# femtoUSB_r1_0_1-rgb.net
KiCad netlist of a schematic drawn in EAGLE
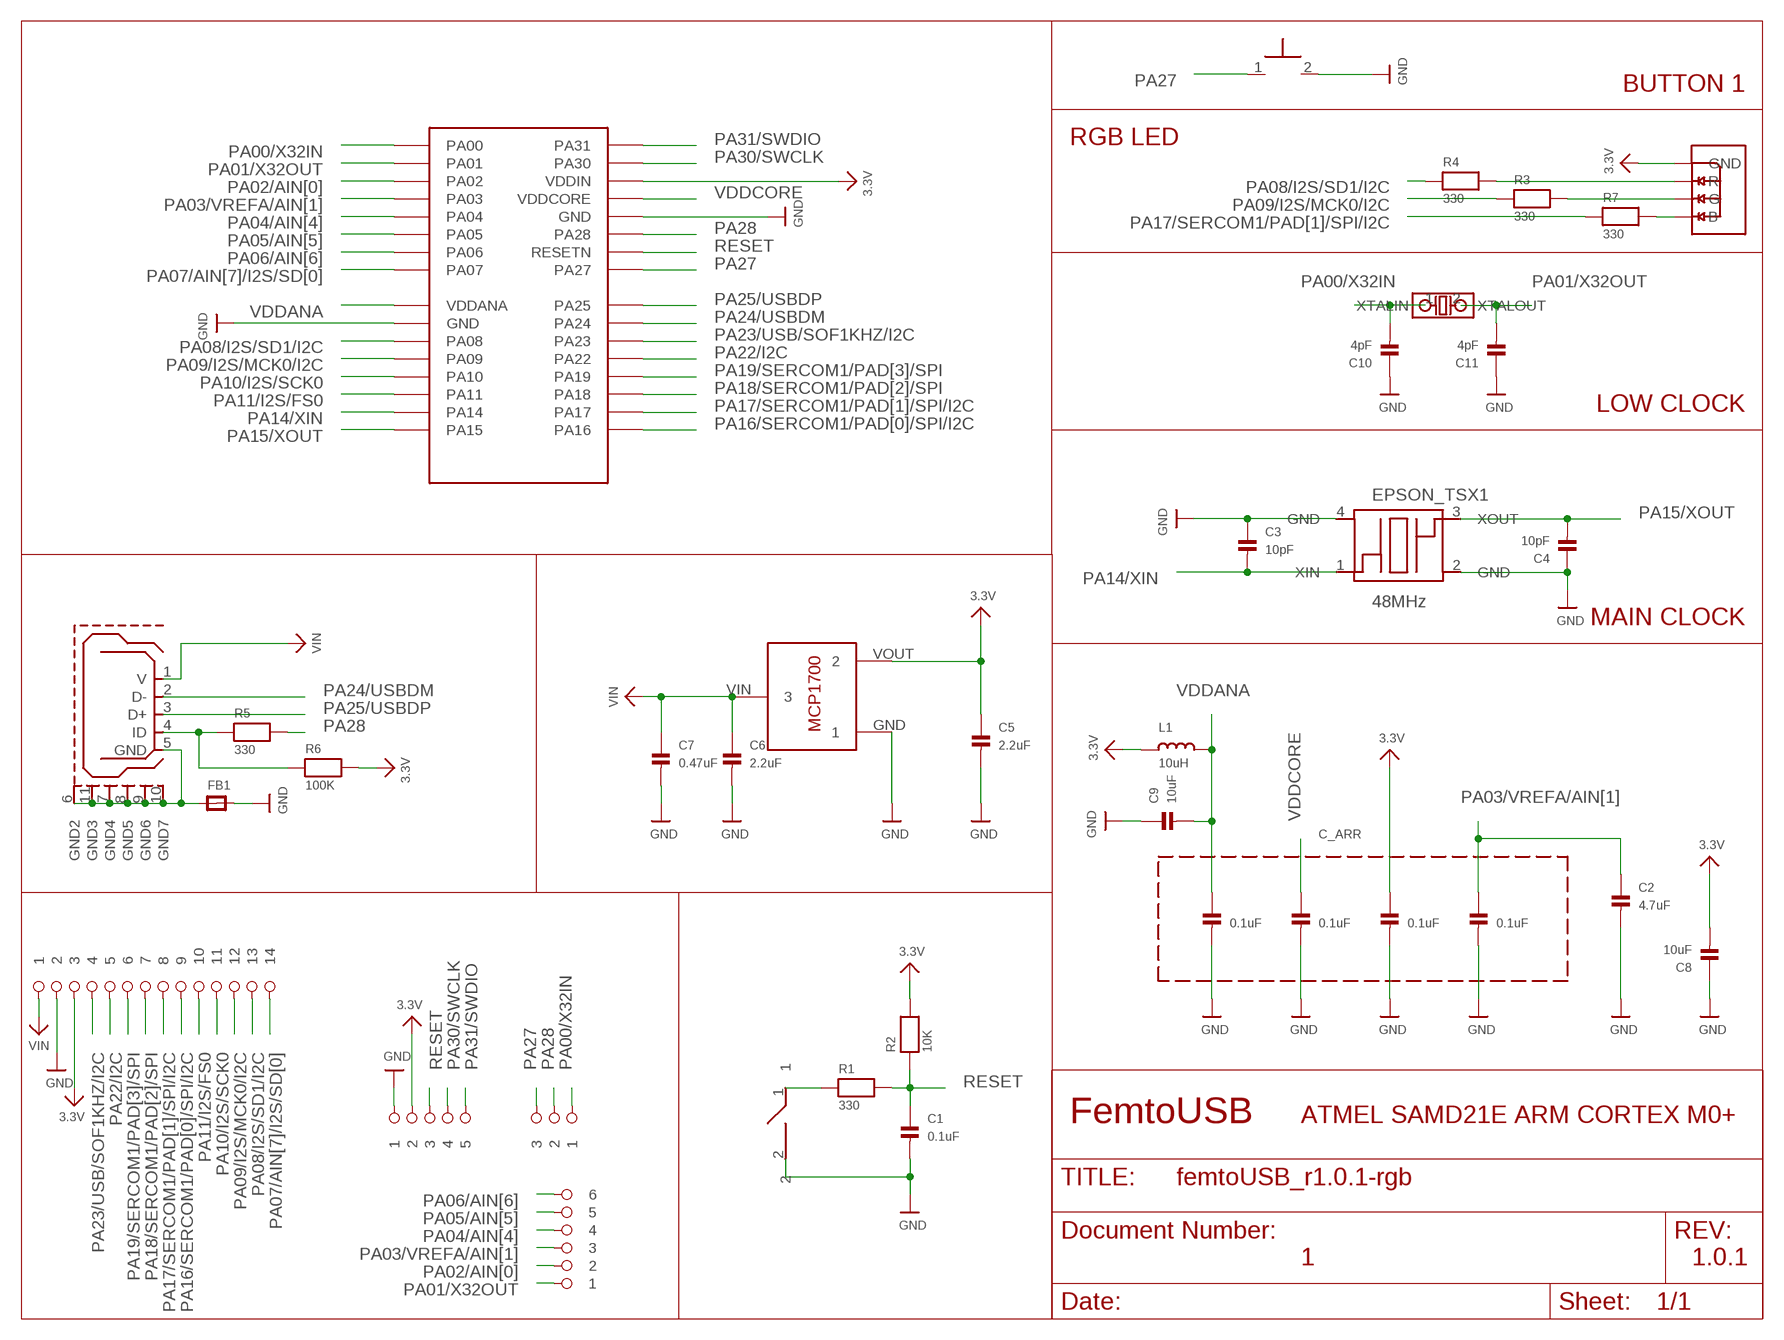
[diagram p0: schematic, sheet 1]

(export (version "E")
  (design (tool "Eeschema 10.0.6"))
  (components
    (comp (ref "BTN_BOOT")
      (value "TACTILE_SWITCH_NO_GND_NO_BOSS")
      (footprint "eagle-import:SIDE_ACT_NO_GND_NO_BOSS")
      (libsource (lib "eagle-import") (part "TACTILE_SWITCH_NO_GND_NO_BOSS"))
    )
    (comp (ref "C1")
      (value "0.1uF")
      (footprint "eagle-import:_0402MP")
      (libsource (lib "eagle-import") (part "CAP_CERAMIC_0402MP"))
    )
    (comp (ref "C2")
      (value "4.7uF")
      (footprint "eagle-import:_0402MP")
      (libsource (lib "eagle-import") (part "CAP_CERAMIC_0402MP"))
    )
    (comp (ref "C3")
      (value "10pF")
      (footprint "eagle-import:_0402MP")
      (libsource (lib "eagle-import") (part "CAP_CERAMIC_0402MP"))
    )
    (comp (ref "C4")
      (value "10pF")
      (footprint "eagle-import:_0402MP")
      (libsource (lib "eagle-import") (part "CAP_CERAMIC_0402MP"))
    )
    (comp (ref "C5")
      (value "2.2uF")
      (footprint "eagle-import:_0402MP")
      (libsource (lib "eagle-import") (part "CAP_CERAMIC_0402MP"))
    )
    (comp (ref "C6")
      (value "2.2uF")
      (footprint "eagle-import:_0402MP")
      (libsource (lib "eagle-import") (part "CAP_CERAMIC_0402MP"))
    )
    (comp (ref "C7")
      (value "0.47uF")
      (footprint "eagle-import:_0402MP")
      (libsource (lib "eagle-import") (part "CAP_CERAMIC_0402MP"))
    )
    (comp (ref "C8")
      (value "10uF")
      (footprint "eagle-import:_0402MP")
      (libsource (lib "eagle-import") (part "CAP_CERAMIC_0402MP"))
    )
    (comp (ref "C9")
      (value "10uF")
      (footprint "eagle-import:_0402MP")
      (libsource (lib "eagle-import") (part "CAP_CERAMIC_0402MP"))
    )
    (comp (ref "C10")
      (value "4pF")
      (footprint "eagle-import:_0402MP")
      (libsource (lib "eagle-import") (part "CAP_CERAMIC_0402MP"))
    )
    (comp (ref "C11")
      (value "4pF")
      (footprint "eagle-import:_0402MP")
      (libsource (lib "eagle-import") (part "CAP_CERAMIC_0402MP"))
    )
    (comp (ref "C_ARR")
      (value "0.1uF")
      (footprint "eagle-import:CAPACITOR_ARRAY_1206_MONO_1X4")
      (libsource (lib "eagle-import") (part "KEMET_CERAMIC_CAPACITOR_ARRAY_1X4"))
    )
    (comp (ref "EPSON_TSX1")
      (value "48MHz")
      (footprint "eagle-import:TSX-3225")
      (libsource (lib "eagle-import") (part "TSX-3225"))
    )
    (comp (ref "FB1")
      (value "FERRITE_0603MP")
      (footprint "eagle-import:_0603MP")
      (libsource (lib "eagle-import") (part "FERRITE_0603MP"))
    )
    (comp (ref "IC1")
      (value "ATSAMD21E18A-MUT")
      (footprint "eagle-import:QFN32")
      (libsource (lib "eagle-import") (part "ATSAMD21E18A-MUT"))
    )
    (comp (ref "L1")
      (value "10uH")
      (footprint "eagle-import:_0603MP")
      (libsource (lib "eagle-import") (part "INDUCTOR_0603MP"))
    )
    (comp (ref "LDO_VREG")
      (value "MCP1700T-3302E/TT")
      (footprint "eagle-import:MCP1700T-3302E_TT")
      (libsource (lib "eagle-import") (part "MCP1700T-3302E/TT"))
    )
    (comp (ref "MICRO_B_USB")
      (value "USB_MICROB")
      (footprint "eagle-import:USB_MICROB_PACKAGE")
      (libsource (lib "eagle-import") (part "USB_MICROB"))
    )
    (comp (ref "OSC32K")
      (value "ABS06-107-32.768KHZ-T")
      (footprint "eagle-import:ABS06-107-32.768KHZ-T")
      (libsource (lib "eagle-import") (part "ABS06-107-32.768KHZ-T"))
    )
    (comp (ref "PIN_1X3")
      (value "1X3_ROUND")
      (footprint "eagle-import:1X3_ROUND")
      (libsource (lib "eagle-import") (part "1X3_ROUND"))
    )
    (comp (ref "PIN_1X5")
      (value "1X5_ROUND")
      (footprint "eagle-import:1X5_ROUND")
      (libsource (lib "eagle-import") (part "1X5_ROUND"))
    )
    (comp (ref "PIN_1X6")
      (value "1X6_ROUND")
      (footprint "eagle-import:1X6_ROUND")
      (libsource (lib "eagle-import") (part "1X6_ROUND"))
    )
    (comp (ref "PIN_1X14")
      (value "1X14_ROUND")
      (footprint "eagle-import:1X14_ROUND")
      (libsource (lib "eagle-import") (part "1X14_ROUND"))
    )
    (comp (ref "R1")
      (value "330")
      (footprint "eagle-import:_0402MP")
      (libsource (lib "eagle-import") (part "RESISTOR_0402MP"))
    )
    (comp (ref "R2")
      (value "10K")
      (footprint "eagle-import:_0402MP")
      (libsource (lib "eagle-import") (part "RESISTOR_0402MP"))
    )
    (comp (ref "R3")
      (value "330")
      (footprint "eagle-import:_0402MP")
      (libsource (lib "eagle-import") (part "RESISTOR_0402MP"))
    )
    (comp (ref "R4")
      (value "330")
      (footprint "eagle-import:_0402MP")
      (libsource (lib "eagle-import") (part "RESISTOR_0402MP"))
    )
    (comp (ref "R5")
      (value "330")
      (footprint "eagle-import:_0402MP")
      (libsource (lib "eagle-import") (part "RESISTOR_0402MP"))
    )
    (comp (ref "R6")
      (value "100K")
      (footprint "eagle-import:_0402MP")
      (libsource (lib "eagle-import") (part "RESISTOR_0402MP"))
    )
    (comp (ref "R7")
      (value "330")
      (footprint "eagle-import:_0402MP")
      (libsource (lib "eagle-import") (part "RESISTOR_0402MP"))
    )
    (comp (ref "RGBLED")
      (value "LRTB_R48G")
      (footprint "eagle-import:LRTB_R48G")
      (libsource (lib "eagle-import") (part "LRTB_R48G"))
    )
    (comp (ref "SJ_RESET")
      (value "SPST_SMD")
      (footprint "eagle-import:SPST_SMD")
      (libsource (lib "eagle-import") (part "SPST_SMD"))
    )
  )
  (nets
    (net (code "1") (name "/PA00{slash}X32IN") (class "Default")
      (node (ref "C10") (pin "2") (pinfunction "P$2_2") (pintype "passive"))
      (node (ref "IC1") (pin "1") (pinfunction "PA00_1") (pintype "bidirectional"))
      (node (ref "OSC32K") (pin "1") (pinfunction "XTALIN_1") (pintype "bidirectional"))
      (node (ref "PIN_1X3") (pin "P$1") (pinfunction "1_P$1") (pintype "bidirectional"))
    )
    (net (code "2") (name "/PA01{slash}X32OUT") (class "Default")
      (node (ref "C11") (pin "2") (pinfunction "P$2_2") (pintype "passive"))
      (node (ref "IC1") (pin "2") (pinfunction "PA01_2") (pintype "bidirectional"))
      (node (ref "OSC32K") (pin "2") (pinfunction "XTALOUT_2") (pintype "bidirectional"))
      (node (ref "PIN_1X6") (pin "P$1") (pinfunction "1_P$1") (pintype "bidirectional"))
    )
    (net (code "3") (name "/PA02{slash}AIN[0]") (class "Default")
      (node (ref "IC1") (pin "3") (pinfunction "PA02_3") (pintype "bidirectional"))
      (node (ref "PIN_1X6") (pin "P$2") (pinfunction "2_P$2") (pintype "bidirectional"))
    )
    (net (code "4") (name "/PA03{slash}VREFA{slash}AIN[1]") (class "Default")
      (node (ref "C2") (pin "1") (pinfunction "P$1_1") (pintype "passive"))
      (node (ref "C_ARR") (pin "7") (pinfunction "P$7_7") (pintype "passive"))
      (node (ref "IC1") (pin "4") (pinfunction "PA03_4") (pintype "bidirectional"))
      (node (ref "PIN_1X6") (pin "P$3") (pinfunction "3_P$3") (pintype "bidirectional"))
    )
    (net (code "5") (name "/PA04{slash}AIN[4]") (class "Default")
      (node (ref "IC1") (pin "5") (pinfunction "PA04_5") (pintype "bidirectional"))
      (node (ref "PIN_1X6") (pin "P$4") (pinfunction "4_P$4") (pintype "bidirectional"))
    )
    (net (code "6") (name "/PA05{slash}AIN[5]") (class "Default")
      (node (ref "IC1") (pin "6") (pinfunction "PA05_6") (pintype "bidirectional"))
      (node (ref "PIN_1X6") (pin "P$5") (pinfunction "5_P$5") (pintype "bidirectional"))
    )
    (net (code "7") (name "/PA06{slash}AIN[6]") (class "Default")
      (node (ref "IC1") (pin "7") (pinfunction "PA06_7") (pintype "bidirectional"))
      (node (ref "PIN_1X6") (pin "P$6") (pinfunction "6_P$6") (pintype "bidirectional"))
    )
    (net (code "8") (name "/PA07{slash}AIN[7]{slash}I2S{slash}SD[0]") (class "Default")
      (node (ref "IC1") (pin "8") (pinfunction "PA07_8") (pintype "bidirectional"))
      (node (ref "PIN_1X14") (pin "P$14") (pinfunction "14_P$14") (pintype "bidirectional"))
    )
    (net (code "9") (name "/PA08{slash}I2S{slash}SD1{slash}I2C") (class "Default")
      (node (ref "IC1") (pin "11") (pinfunction "PA08_11") (pintype "bidirectional"))
      (node (ref "PIN_1X14") (pin "P$13") (pinfunction "13_P$13") (pintype "bidirectional"))
      (node (ref "R4") (pin "1") (pinfunction "1_1") (pintype "passive"))
    )
    (net (code "10") (name "/PA09{slash}I2S{slash}MCK0{slash}I2C") (class "Default")
      (node (ref "IC1") (pin "12") (pinfunction "PA09_12") (pintype "bidirectional"))
      (node (ref "PIN_1X14") (pin "P$12") (pinfunction "12_P$12") (pintype "bidirectional"))
      (node (ref "R3") (pin "1") (pinfunction "1_1") (pintype "passive"))
    )
    (net (code "11") (name "/PA10{slash}I2S{slash}SCK0") (class "Default")
      (node (ref "IC1") (pin "13") (pinfunction "PA10_13") (pintype "bidirectional"))
      (node (ref "PIN_1X14") (pin "P$11") (pinfunction "11_P$11") (pintype "bidirectional"))
    )
    (net (code "12") (name "/PA11{slash}I2S{slash}FS0") (class "Default")
      (node (ref "IC1") (pin "14") (pinfunction "PA11_14") (pintype "bidirectional"))
      (node (ref "PIN_1X14") (pin "P$10") (pinfunction "10_P$10") (pintype "bidirectional"))
    )
    (net (code "13") (name "/PA14{slash}XIN") (class "Default")
      (node (ref "C3") (pin "2") (pinfunction "P$2_2") (pintype "passive"))
      (node (ref "EPSON_TSX1") (pin "1") (pinfunction "XIN_1") (pintype "bidirectional"))
      (node (ref "IC1") (pin "15") (pinfunction "PA14_15") (pintype "bidirectional"))
    )
    (net (code "14") (name "/PA15{slash}XOUT") (class "Default")
      (node (ref "C4") (pin "2") (pinfunction "P$2_2") (pintype "passive"))
      (node (ref "EPSON_TSX1") (pin "3") (pinfunction "XOUT_3") (pintype "bidirectional"))
      (node (ref "IC1") (pin "16") (pinfunction "PA15_16") (pintype "bidirectional"))
    )
    (net (code "15") (name "/PA16{slash}SERCOM1{slash}PAD[0]{slash}SPI{slash}I2C") (class "Default")
      (node (ref "IC1") (pin "17") (pinfunction "PA16_17") (pintype "bidirectional"))
      (node (ref "PIN_1X14") (pin "P$9") (pinfunction "9_P$9") (pintype "bidirectional"))
    )
    (net (code "16") (name "/PA17{slash}SERCOM1{slash}PAD[1]{slash}SPI{slash}I2C") (class "Default")
      (node (ref "IC1") (pin "18") (pinfunction "PA17_18") (pintype "bidirectional"))
      (node (ref "PIN_1X14") (pin "P$8") (pinfunction "8_P$8") (pintype "bidirectional"))
      (node (ref "R7") (pin "1") (pinfunction "1_1") (pintype "passive"))
    )
    (net (code "17") (name "/PA18{slash}SERCOM1{slash}PAD[2]{slash}SPI") (class "Default")
      (node (ref "IC1") (pin "19") (pinfunction "PA18_19") (pintype "bidirectional"))
      (node (ref "PIN_1X14") (pin "P$7") (pinfunction "7_P$7") (pintype "bidirectional"))
    )
    (net (code "18") (name "/PA19{slash}SERCOM1{slash}PAD[3]{slash}SPI") (class "Default")
      (node (ref "IC1") (pin "20") (pinfunction "PA19_20") (pintype "bidirectional"))
      (node (ref "PIN_1X14") (pin "P$6") (pinfunction "6_P$6") (pintype "bidirectional"))
    )
    (net (code "19") (name "/PA22{slash}I2C") (class "Default")
      (node (ref "IC1") (pin "21") (pinfunction "PA22_21") (pintype "bidirectional"))
      (node (ref "PIN_1X14") (pin "P$5") (pinfunction "5_P$5") (pintype "bidirectional"))
    )
    (net (code "20") (name "/PA23{slash}USB{slash}SOF1KHZ{slash}I2C") (class "Default")
      (node (ref "IC1") (pin "22") (pinfunction "PA23_22") (pintype "bidirectional"))
      (node (ref "PIN_1X14") (pin "P$4") (pinfunction "4_P$4") (pintype "bidirectional"))
    )
    (net (code "21") (name "/PA24{slash}USBDM") (class "Default")
      (node (ref "IC1") (pin "23") (pinfunction "PA24_23") (pintype "bidirectional"))
      (node (ref "MICRO_B_USB") (pin "2") (pinfunction "D-_2") (pintype "bidirectional"))
    )
    (net (code "22") (name "/PA25{slash}USBDP") (class "Default")
      (node (ref "IC1") (pin "24") (pinfunction "PA25_24") (pintype "bidirectional"))
      (node (ref "MICRO_B_USB") (pin "3") (pinfunction "D+_3") (pintype "bidirectional"))
    )
    (net (code "23") (name "/PA27") (class "Default")
      (node (ref "BTN_BOOT") (pin "1") (pinfunction "1_1") (pintype "bidirectional"))
      (node (ref "IC1") (pin "25") (pinfunction "PA27_25") (pintype "bidirectional"))
      (node (ref "PIN_1X3") (pin "P$3") (pinfunction "3_P$3") (pintype "bidirectional"))
    )
    (net (code "24") (name "/PA28") (class "Default")
      (node (ref "IC1") (pin "27") (pinfunction "PA28_27") (pintype "bidirectional"))
      (node (ref "PIN_1X3") (pin "P$2") (pinfunction "2_P$2") (pintype "bidirectional"))
      (node (ref "R5") (pin "2") (pinfunction "2_2") (pintype "passive"))
    )
    (net (code "25") (name "/PA30{slash}SWCLK") (class "Default")
      (node (ref "IC1") (pin "31") (pinfunction "PA30_31") (pintype "bidirectional"))
      (node (ref "PIN_1X5") (pin "P$4") (pinfunction "4_P$4") (pintype "bidirectional"))
    )
    (net (code "26") (name "/PA31{slash}SWDIO") (class "Default")
      (node (ref "IC1") (pin "32") (pinfunction "PA31_32") (pintype "bidirectional"))
      (node (ref "PIN_1X5") (pin "P$5") (pinfunction "5_P$5") (pintype "bidirectional"))
    )
    (net (code "27") (name "/RESET") (class "Default")
      (node (ref "C1") (pin "1") (pinfunction "P$1_1") (pintype "passive"))
      (node (ref "IC1") (pin "26") (pinfunction "RESETN_26") (pintype "bidirectional"))
      (node (ref "PIN_1X5") (pin "P$3") (pinfunction "3_P$3") (pintype "bidirectional"))
      (node (ref "R1") (pin "2") (pinfunction "2_2") (pintype "passive"))
      (node (ref "R2") (pin "1") (pinfunction "1_1") (pintype "passive"))
    )
    (net (code "28") (name "/VDDANA") (class "Default")
      (node (ref "C9") (pin "2") (pinfunction "P$2_2") (pintype "passive"))
      (node (ref "C_ARR") (pin "1") (pinfunction "P$1_1") (pintype "passive"))
      (node (ref "IC1") (pin "9") (pinfunction "VDDANA_9") (pintype "bidirectional"))
      (node (ref "L1") (pin "2") (pinfunction "2_2") (pintype "passive"))
    )
    (net (code "29") (name "/VDDCORE") (class "Default")
      (node (ref "C_ARR") (pin "3") (pinfunction "P$3_3") (pintype "passive"))
      (node (ref "IC1") (pin "29") (pinfunction "VDDCORE_29") (pintype "bidirectional"))
    )
    (net (code "30") (name "3.3V") (class "Default")
      (node (ref "C5") (pin "1") (pinfunction "P$1_1") (pintype "passive"))
      (node (ref "C8") (pin "2") (pinfunction "P$2_2") (pintype "passive"))
      (node (ref "C_ARR") (pin "5") (pinfunction "P$5_5") (pintype "passive"))
      (node (ref "IC1") (pin "30") (pinfunction "VDDIN_30") (pintype "bidirectional"))
      (node (ref "L1") (pin "1") (pinfunction "1_1") (pintype "passive"))
      (node (ref "LDO_VREG") (pin "VOUT") (pinfunction "2_VOUT") (pintype "bidirectional"))
      (node (ref "PIN_1X14") (pin "P$3") (pinfunction "3_P$3") (pintype "bidirectional"))
      (node (ref "PIN_1X5") (pin "P$2") (pinfunction "2_P$2") (pintype "bidirectional"))
      (node (ref "R2") (pin "2") (pinfunction "2_2") (pintype "passive"))
      (node (ref "R6") (pin "2") (pinfunction "2_2") (pintype "passive"))
      (node (ref "RGBLED") (pin "1") (pinfunction "GND_1") (pintype "bidirectional"))
    )
    (net (code "31") (name "GND") (class "Default")
      (node (ref "BTN_BOOT") (pin "2") (pinfunction "2_2") (pintype "bidirectional"))
      (node (ref "C1") (pin "2") (pinfunction "P$2_2") (pintype "passive"))
      (node (ref "C10") (pin "1") (pinfunction "P$1_1") (pintype "passive"))
      (node (ref "C11") (pin "1") (pinfunction "P$1_1") (pintype "passive"))
      (node (ref "C2") (pin "2") (pinfunction "P$2_2") (pintype "passive"))
      (node (ref "C3") (pin "1") (pinfunction "P$1_1") (pintype "passive"))
      (node (ref "C4") (pin "1") (pinfunction "P$1_1") (pintype "passive"))
      (node (ref "C5") (pin "2") (pinfunction "P$2_2") (pintype "passive"))
      (node (ref "C6") (pin "2") (pinfunction "P$2_2") (pintype "passive"))
      (node (ref "C7") (pin "2") (pinfunction "P$2_2") (pintype "passive"))
      (node (ref "C8") (pin "1") (pinfunction "P$1_1") (pintype "passive"))
      (node (ref "C9") (pin "1") (pinfunction "P$1_1") (pintype "passive"))
      (node (ref "C_ARR") (pin "2") (pinfunction "P$2_2") (pintype "passive"))
      (node (ref "C_ARR") (pin "4") (pinfunction "P$4_4") (pintype "passive"))
      (node (ref "C_ARR") (pin "6") (pinfunction "P$6_6") (pintype "passive"))
      (node (ref "C_ARR") (pin "8") (pinfunction "P$8_8") (pintype "passive"))
      (node (ref "EPSON_TSX1") (pin "2") (pinfunction "GND_2") (pintype "bidirectional"))
      (node (ref "EPSON_TSX1") (pin "4") (pinfunction "GND_4") (pintype "bidirectional"))
      (node (ref "FB1") (pin "2") (pinfunction "P$2_2") (pintype "passive"))
      (node (ref "IC1") (pin "10") (pinfunction "GND_10") (pintype "bidirectional"))
      (node (ref "IC1") (pin "28") (pinfunction "GND_28") (pintype "bidirectional"))
      (node (ref "LDO_VREG") (pin "GND") (pinfunction "1_GND") (pintype "bidirectional"))
      (node (ref "PIN_1X14") (pin "P$2") (pinfunction "2_P$2") (pintype "bidirectional"))
      (node (ref "PIN_1X5") (pin "P$1") (pinfunction "1_P$1") (pintype "bidirectional"))
      (node (ref "SJ_RESET") (pin "2") (pinfunction "2_2") (pintype "bidirectional"))
    )
    (net (code "32") (name "Net-(FB1-P$1)") (class "Default")
      (node (ref "FB1") (pin "1") (pinfunction "P$1_1") (pintype "passive"))
      (node (ref "MICRO_B_USB") (pin "10") (pinfunction "GND7_10") (pintype "bidirectional"))
      (node (ref "MICRO_B_USB") (pin "11") (pinfunction "GND3_11") (pintype "bidirectional"))
      (node (ref "MICRO_B_USB") (pin "5") (pinfunction "GND_5") (pintype "bidirectional"))
      (node (ref "MICRO_B_USB") (pin "6") (pinfunction "GND2_6") (pintype "bidirectional"))
      (node (ref "MICRO_B_USB") (pin "7") (pinfunction "GND4_7") (pintype "bidirectional"))
      (node (ref "MICRO_B_USB") (pin "8") (pinfunction "GND5_8") (pintype "bidirectional"))
      (node (ref "MICRO_B_USB") (pin "9") (pinfunction "GND6_9") (pintype "bidirectional"))
    )
    (net (code "33") (name "Net-(MICRO_B_USB-ID)") (class "Default")
      (node (ref "MICRO_B_USB") (pin "4") (pinfunction "ID_4") (pintype "bidirectional"))
      (node (ref "R5") (pin "1") (pinfunction "1_1") (pintype "passive"))
      (node (ref "R6") (pin "1") (pinfunction "1_1") (pintype "passive"))
    )
    (net (code "34") (name "Net-(R1-Pad1)") (class "Default")
      (node (ref "R1") (pin "1") (pinfunction "1_1") (pintype "passive"))
      (node (ref "SJ_RESET") (pin "1") (pinfunction "1_1") (pintype "bidirectional"))
    )
    (net (code "35") (name "Net-(RGBLED-B)") (class "Default")
      (node (ref "R7") (pin "2") (pinfunction "2_2") (pintype "passive"))
      (node (ref "RGBLED") (pin "4") (pinfunction "B_4") (pintype "bidirectional"))
    )
    (net (code "36") (name "Net-(RGBLED-G)") (class "Default")
      (node (ref "R3") (pin "2") (pinfunction "2_2") (pintype "passive"))
      (node (ref "RGBLED") (pin "3") (pinfunction "G_3") (pintype "bidirectional"))
    )
    (net (code "37") (name "Net-(RGBLED-R)") (class "Default")
      (node (ref "R4") (pin "2") (pinfunction "2_2") (pintype "passive"))
      (node (ref "RGBLED") (pin "2") (pinfunction "R_2") (pintype "bidirectional"))
    )
    (net (code "38") (name "VIN") (class "Default")
      (node (ref "C6") (pin "1") (pinfunction "P$1_1") (pintype "passive"))
      (node (ref "C7") (pin "1") (pinfunction "P$1_1") (pintype "passive"))
      (node (ref "LDO_VREG") (pin "VIN") (pinfunction "3_VIN") (pintype "bidirectional"))
      (node (ref "MICRO_B_USB") (pin "1") (pinfunction "V_1") (pintype "bidirectional"))
      (node (ref "PIN_1X14") (pin "P$1") (pinfunction "1_P$1") (pintype "bidirectional"))
    )
  )
)
